# primer_piso.net
KiCad netlist of a schematic drawn in EAGLE
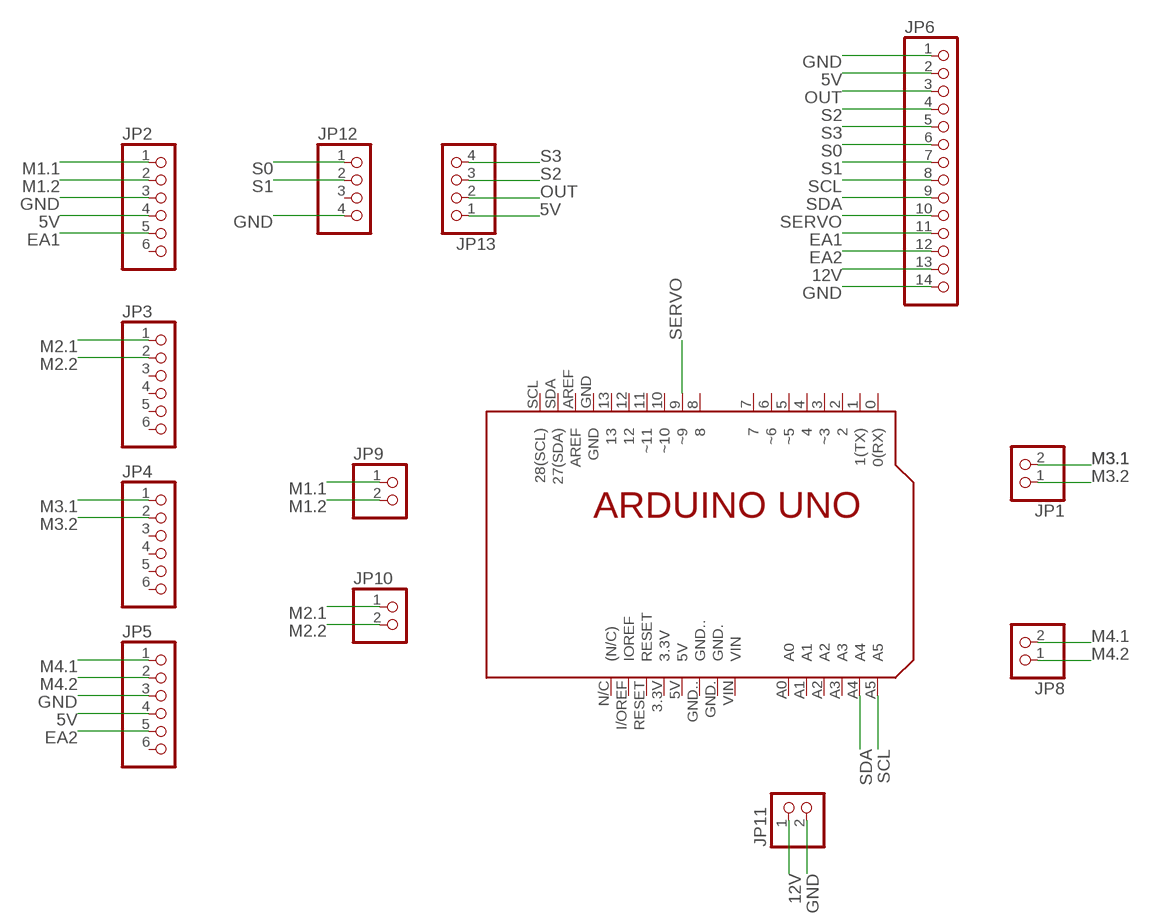
[diagram p0: schematic, sheet 1]

(export (version "E")
  (design (tool "Eeschema 10.0.6"))
  (components
    (comp (ref "JP1")
      (value "PINHD-1X2")
      (footprint "eagle-import:1X02")
      (libsource (lib "eagle-import") (part "PINHD-1X2"))
    )
    (comp (ref "JP2")
      (value "PINHD-1X6")
      (footprint "eagle-import:1X06")
      (libsource (lib "eagle-import") (part "PINHD-1X6"))
    )
    (comp (ref "JP3")
      (value "PINHD-1X6")
      (footprint "eagle-import:1X06")
      (libsource (lib "eagle-import") (part "PINHD-1X6"))
    )
    (comp (ref "JP4")
      (value "PINHD-1X6")
      (footprint "eagle-import:1X06")
      (libsource (lib "eagle-import") (part "PINHD-1X6"))
    )
    (comp (ref "JP5")
      (value "PINHD-1X6")
      (footprint "eagle-import:1X06")
      (libsource (lib "eagle-import") (part "PINHD-1X6"))
    )
    (comp (ref "JP6")
      (value "PINHD-1X14")
      (footprint "eagle-import:1X14")
      (libsource (lib "eagle-import") (part "PINHD-1X14"))
    )
    (comp (ref "JP8")
      (value "PINHD-1X2")
      (footprint "eagle-import:1X02")
      (libsource (lib "eagle-import") (part "PINHD-1X2"))
    )
    (comp (ref "JP9")
      (value "PINHD-1X2")
      (footprint "eagle-import:1X02")
      (libsource (lib "eagle-import") (part "PINHD-1X2"))
    )
    (comp (ref "JP10")
      (value "PINHD-1X2")
      (footprint "eagle-import:1X02")
      (libsource (lib "eagle-import") (part "PINHD-1X2"))
    )
    (comp (ref "JP11")
      (value "PINHD-1X2")
      (footprint "eagle-import:1X02")
      (libsource (lib "eagle-import") (part "PINHD-1X2"))
    )
    (comp (ref "JP12")
      (value "PINHD-1X4")
      (footprint "eagle-import:1X04")
      (libsource (lib "eagle-import") (part "PINHD-1X4"))
    )
    (comp (ref "JP13")
      (value "PINHD-1X4")
      (footprint "eagle-import:1X04")
      (libsource (lib "eagle-import") (part "PINHD-1X4"))
    )
    (comp (ref "UNO1")
      (value "UNO")
      (footprint "eagle-import:UNO")
      (libsource (lib "eagle-import") (part "UNO"))
    )
  )
  (nets
    (net (code "1") (name "/5V") (class "Default")
      (node (ref "JP13") (pin "1") (pinfunction "1_1") (pintype "passive"))
      (node (ref "JP2") (pin "4") (pinfunction "4_4") (pintype "passive"))
      (node (ref "JP5") (pin "4") (pinfunction "4_4") (pintype "passive"))
      (node (ref "JP6") (pin "2") (pinfunction "2_2") (pintype "passive"))
    )
    (net (code "2") (name "/12V") (class "Default")
      (node (ref "JP11") (pin "1") (pinfunction "1_1") (pintype "passive"))
      (node (ref "JP6") (pin "13") (pinfunction "13_13") (pintype "passive"))
    )
    (net (code "3") (name "/EA1") (class "Default")
      (node (ref "JP2") (pin "5") (pinfunction "5_5") (pintype "passive"))
      (node (ref "JP6") (pin "11") (pinfunction "11_11") (pintype "passive"))
    )
    (net (code "4") (name "/EA2") (class "Default")
      (node (ref "JP5") (pin "5") (pinfunction "5_5") (pintype "passive"))
      (node (ref "JP6") (pin "12") (pinfunction "12_12") (pintype "passive"))
    )
    (net (code "5") (name "/GND") (class "Default")
      (node (ref "JP11") (pin "2") (pinfunction "2_2") (pintype "passive"))
      (node (ref "JP12") (pin "4") (pinfunction "4_4") (pintype "passive"))
      (node (ref "JP2") (pin "3") (pinfunction "3_3") (pintype "passive"))
      (node (ref "JP5") (pin "3") (pinfunction "3_3") (pintype "passive"))
      (node (ref "JP6") (pin "1") (pinfunction "1_1") (pintype "passive"))
      (node (ref "JP6") (pin "14") (pinfunction "14_14") (pintype "passive"))
    )
    (net (code "6") (name "/M1.1") (class "Default")
      (node (ref "JP2") (pin "1") (pinfunction "1_1") (pintype "passive"))
      (node (ref "JP9") (pin "1") (pinfunction "1_1") (pintype "passive"))
    )
    (net (code "7") (name "/M1.2") (class "Default")
      (node (ref "JP2") (pin "2") (pinfunction "2_2") (pintype "passive"))
      (node (ref "JP9") (pin "2") (pinfunction "2_2") (pintype "passive"))
    )
    (net (code "8") (name "/M2.1") (class "Default")
      (node (ref "JP10") (pin "1") (pinfunction "1_1") (pintype "passive"))
      (node (ref "JP3") (pin "1") (pinfunction "1_1") (pintype "passive"))
    )
    (net (code "9") (name "/M2.2") (class "Default")
      (node (ref "JP10") (pin "2") (pinfunction "2_2") (pintype "passive"))
      (node (ref "JP3") (pin "2") (pinfunction "2_2") (pintype "passive"))
    )
    (net (code "10") (name "/M3.1") (class "Default")
      (node (ref "JP1") (pin "2") (pinfunction "2_2") (pintype "passive"))
      (node (ref "JP4") (pin "1") (pinfunction "1_1") (pintype "passive"))
    )
    (net (code "11") (name "/M3.2") (class "Default")
      (node (ref "JP1") (pin "1") (pinfunction "1_1") (pintype "passive"))
      (node (ref "JP4") (pin "2") (pinfunction "2_2") (pintype "passive"))
    )
    (net (code "12") (name "/M4.1") (class "Default")
      (node (ref "JP5") (pin "1") (pinfunction "1_1") (pintype "passive"))
      (node (ref "JP8") (pin "2") (pinfunction "2_2") (pintype "passive"))
    )
    (net (code "13") (name "/M4.2") (class "Default")
      (node (ref "JP5") (pin "2") (pinfunction "2_2") (pintype "passive"))
      (node (ref "JP8") (pin "1") (pinfunction "1_1") (pintype "passive"))
    )
    (net (code "14") (name "/OUT") (class "Default")
      (node (ref "JP13") (pin "2") (pinfunction "2_2") (pintype "passive"))
      (node (ref "JP6") (pin "3") (pinfunction "3_3") (pintype "passive"))
    )
    (net (code "15") (name "/S0") (class "Default")
      (node (ref "JP12") (pin "1") (pinfunction "1_1") (pintype "passive"))
      (node (ref "JP6") (pin "6") (pinfunction "6_6") (pintype "passive"))
    )
    (net (code "16") (name "/S1") (class "Default")
      (node (ref "JP12") (pin "2") (pinfunction "2_2") (pintype "passive"))
      (node (ref "JP6") (pin "7") (pinfunction "7_7") (pintype "passive"))
    )
    (net (code "17") (name "/S2") (class "Default")
      (node (ref "JP13") (pin "3") (pinfunction "3_3") (pintype "passive"))
      (node (ref "JP6") (pin "4") (pinfunction "4_4") (pintype "passive"))
    )
    (net (code "18") (name "/S3") (class "Default")
      (node (ref "JP13") (pin "4") (pinfunction "4_4") (pintype "passive"))
      (node (ref "JP6") (pin "5") (pinfunction "5_5") (pintype "passive"))
    )
    (net (code "19") (name "/SCL") (class "Default")
      (node (ref "JP6") (pin "8") (pinfunction "8_8") (pintype "passive"))
      (node (ref "UNO1") (pin "A5") (pinfunction "A5_A5") (pintype "bidirectional"))
    )
    (net (code "20") (name "/SDA") (class "Default")
      (node (ref "JP6") (pin "9") (pinfunction "9_9") (pintype "passive"))
      (node (ref "UNO1") (pin "A4") (pinfunction "A4_A4") (pintype "bidirectional"))
    )
    (net (code "21") (name "/SERVO") (class "Default")
      (node (ref "JP6") (pin "10") (pinfunction "10_10") (pintype "passive"))
      (node (ref "UNO1") (pin "9") (pinfunction "~{9}_9") (pintype "bidirectional"))
    )
    (net (code "22") (name "unconnected-(JP2-Pad6)") (class "Default")
      (node (ref "JP2") (pin "6") (pinfunction "6_6") (pintype "passive"))
    )
    (net (code "23") (name "unconnected-(JP3-Pad3)") (class "Default")
      (node (ref "JP3") (pin "3") (pinfunction "3_3") (pintype "passive"))
    )
    (net (code "24") (name "unconnected-(JP3-Pad4)") (class "Default")
      (node (ref "JP3") (pin "4") (pinfunction "4_4") (pintype "passive"))
    )
    (net (code "25") (name "unconnected-(JP3-Pad5)") (class "Default")
      (node (ref "JP3") (pin "5") (pinfunction "5_5") (pintype "passive"))
    )
    (net (code "26") (name "unconnected-(JP3-Pad6)") (class "Default")
      (node (ref "JP3") (pin "6") (pinfunction "6_6") (pintype "passive"))
    )
    (net (code "27") (name "unconnected-(JP4-Pad3)") (class "Default")
      (node (ref "JP4") (pin "3") (pinfunction "3_3") (pintype "passive"))
    )
    (net (code "28") (name "unconnected-(JP4-Pad4)") (class "Default")
      (node (ref "JP4") (pin "4") (pinfunction "4_4") (pintype "passive"))
    )
    (net (code "29") (name "unconnected-(JP4-Pad5)") (class "Default")
      (node (ref "JP4") (pin "5") (pinfunction "5_5") (pintype "passive"))
    )
    (net (code "30") (name "unconnected-(JP4-Pad6)") (class "Default")
      (node (ref "JP4") (pin "6") (pinfunction "6_6") (pintype "passive"))
    )
    (net (code "31") (name "unconnected-(JP5-Pad6)") (class "Default")
      (node (ref "JP5") (pin "6") (pinfunction "6_6") (pintype "passive"))
    )
    (net (code "32") (name "unconnected-(JP12-Pad3)") (class "Default")
      (node (ref "JP12") (pin "3") (pinfunction "3_3") (pintype "passive"))
    )
    (net (code "33") (name "unconnected-(UNO1-(N{slash}C)-PadN{slash}C)") (class "Default")
      (node (ref "UNO1") (pin "N/C") (pinfunction "(N/C)_N/C") (pintype "bidirectional"))
    )
    (net (code "34") (name "unconnected-(UNO1-0(RX)-Pad0)") (class "Default")
      (node (ref "UNO1") (pin "0") (pinfunction "0(RX)_0") (pintype "bidirectional"))
    )
    (net (code "35") (name "unconnected-(UNO1-1(TX)-Pad1)") (class "Default")
      (node (ref "UNO1") (pin "1") (pinfunction "1(TX)_1") (pintype "bidirectional"))
    )
    (net (code "36") (name "unconnected-(UNO1-27(SDA)-PadSDA)") (class "Default")
      (node (ref "UNO1") (pin "SDA") (pinfunction "27(SDA)_SDA") (pintype "bidirectional"))
    )
    (net (code "37") (name "unconnected-(UNO1-28(SCL)-PadSCL)") (class "Default")
      (node (ref "UNO1") (pin "SCL") (pinfunction "28(SCL)_SCL") (pintype "bidirectional"))
    )
    (net (code "38") (name "unconnected-(UNO1-IOREF-PadI{slash}OREF)") (class "Default")
      (node (ref "UNO1") (pin "I/OREF") (pinfunction "IOREF_I/OREF") (pintype "bidirectional"))
    )
    (net (code "39") (name "unconnected-(UNO1-Pad2)") (class "Default")
      (node (ref "UNO1") (pin "2") (pinfunction "2_2") (pintype "bidirectional"))
    )
    (net (code "40") (name "unconnected-(UNO1-Pad3.3V)") (class "Default")
      (node (ref "UNO1") (pin "3.3V") (pinfunction "3.3V_3.3V") (pintype "bidirectional"))
    )
    (net (code "41") (name "unconnected-(UNO1-Pad4)") (class "Default")
      (node (ref "UNO1") (pin "4") (pinfunction "4_4") (pintype "bidirectional"))
    )
    (net (code "42") (name "unconnected-(UNO1-Pad5V)") (class "Default")
      (node (ref "UNO1") (pin "5V") (pinfunction "5V_5V") (pintype "bidirectional"))
    )
    (net (code "43") (name "unconnected-(UNO1-Pad7)") (class "Default")
      (node (ref "UNO1") (pin "7") (pinfunction "7_7") (pintype "bidirectional"))
    )
    (net (code "44") (name "unconnected-(UNO1-Pad8)") (class "Default")
      (node (ref "UNO1") (pin "8") (pinfunction "8_8") (pintype "bidirectional"))
    )
    (net (code "45") (name "unconnected-(UNO1-Pad12)") (class "Default")
      (node (ref "UNO1") (pin "12") (pinfunction "12_12") (pintype "bidirectional"))
    )
    (net (code "46") (name "unconnected-(UNO1-Pad13)") (class "Default")
      (node (ref "UNO1") (pin "13") (pinfunction "13_13") (pintype "bidirectional"))
    )
    (net (code "47") (name "unconnected-(UNO1-PadA0)") (class "Default")
      (node (ref "UNO1") (pin "A0") (pinfunction "A0_A0") (pintype "bidirectional"))
    )
    (net (code "48") (name "unconnected-(UNO1-PadA1)") (class "Default")
      (node (ref "UNO1") (pin "A1") (pinfunction "A1_A1") (pintype "bidirectional"))
    )
    (net (code "49") (name "unconnected-(UNO1-PadA2)") (class "Default")
      (node (ref "UNO1") (pin "A2") (pinfunction "A2_A2") (pintype "bidirectional"))
    )
    (net (code "50") (name "unconnected-(UNO1-PadA3)") (class "Default")
      (node (ref "UNO1") (pin "A3") (pinfunction "A3_A3") (pintype "bidirectional"))
    )
    (net (code "51") (name "unconnected-(UNO1-PadAREF)") (class "Default")
      (node (ref "UNO1") (pin "AREF") (pinfunction "AREF_AREF") (pintype "bidirectional"))
    )
    (net (code "52") (name "unconnected-(UNO1-PadGND)") (class "Default")
      (node (ref "UNO1") (pin "GND") (pinfunction "GND_GND") (pintype "bidirectional"))
    )
    (net (code "53") (name "unconnected-(UNO1-PadGND.)") (class "Default")
      (node (ref "UNO1") (pin "GND.") (pinfunction "GND._GND.") (pintype "bidirectional"))
    )
    (net (code "54") (name "unconnected-(UNO1-PadGND..)") (class "Default")
      (node (ref "UNO1") (pin "GND..") (pinfunction "GND.._GND..") (pintype "bidirectional"))
    )
    (net (code "55") (name "unconnected-(UNO1-PadRESET)") (class "Default")
      (node (ref "UNO1") (pin "RESET") (pinfunction "RESET_RESET") (pintype "bidirectional"))
    )
    (net (code "56") (name "unconnected-(UNO1-PadVIN)") (class "Default")
      (node (ref "UNO1") (pin "VIN") (pinfunction "VIN_VIN") (pintype "bidirectional"))
    )
    (net (code "57") (name "unconnected-(UNO1-~{3}-Pad3)") (class "Default")
      (node (ref "UNO1") (pin "3") (pinfunction "~{3}_3") (pintype "bidirectional"))
    )
    (net (code "58") (name "unconnected-(UNO1-~{5}-Pad5)") (class "Default")
      (node (ref "UNO1") (pin "5") (pinfunction "~{5}_5") (pintype "bidirectional"))
    )
    (net (code "59") (name "unconnected-(UNO1-~{6}-Pad6)") (class "Default")
      (node (ref "UNO1") (pin "6") (pinfunction "~{6}_6") (pintype "bidirectional"))
    )
    (net (code "60") (name "unconnected-(UNO1-~{10}-Pad10)") (class "Default")
      (node (ref "UNO1") (pin "10") (pinfunction "~{10}_10") (pintype "bidirectional"))
    )
    (net (code "61") (name "unconnected-(UNO1-~{11}-Pad11)") (class "Default")
      (node (ref "UNO1") (pin "11") (pinfunction "~{11}_11") (pintype "bidirectional"))
    )
  )
)
